# H08R7.net
KiCad netlist of a schematic drawn in EAGLE
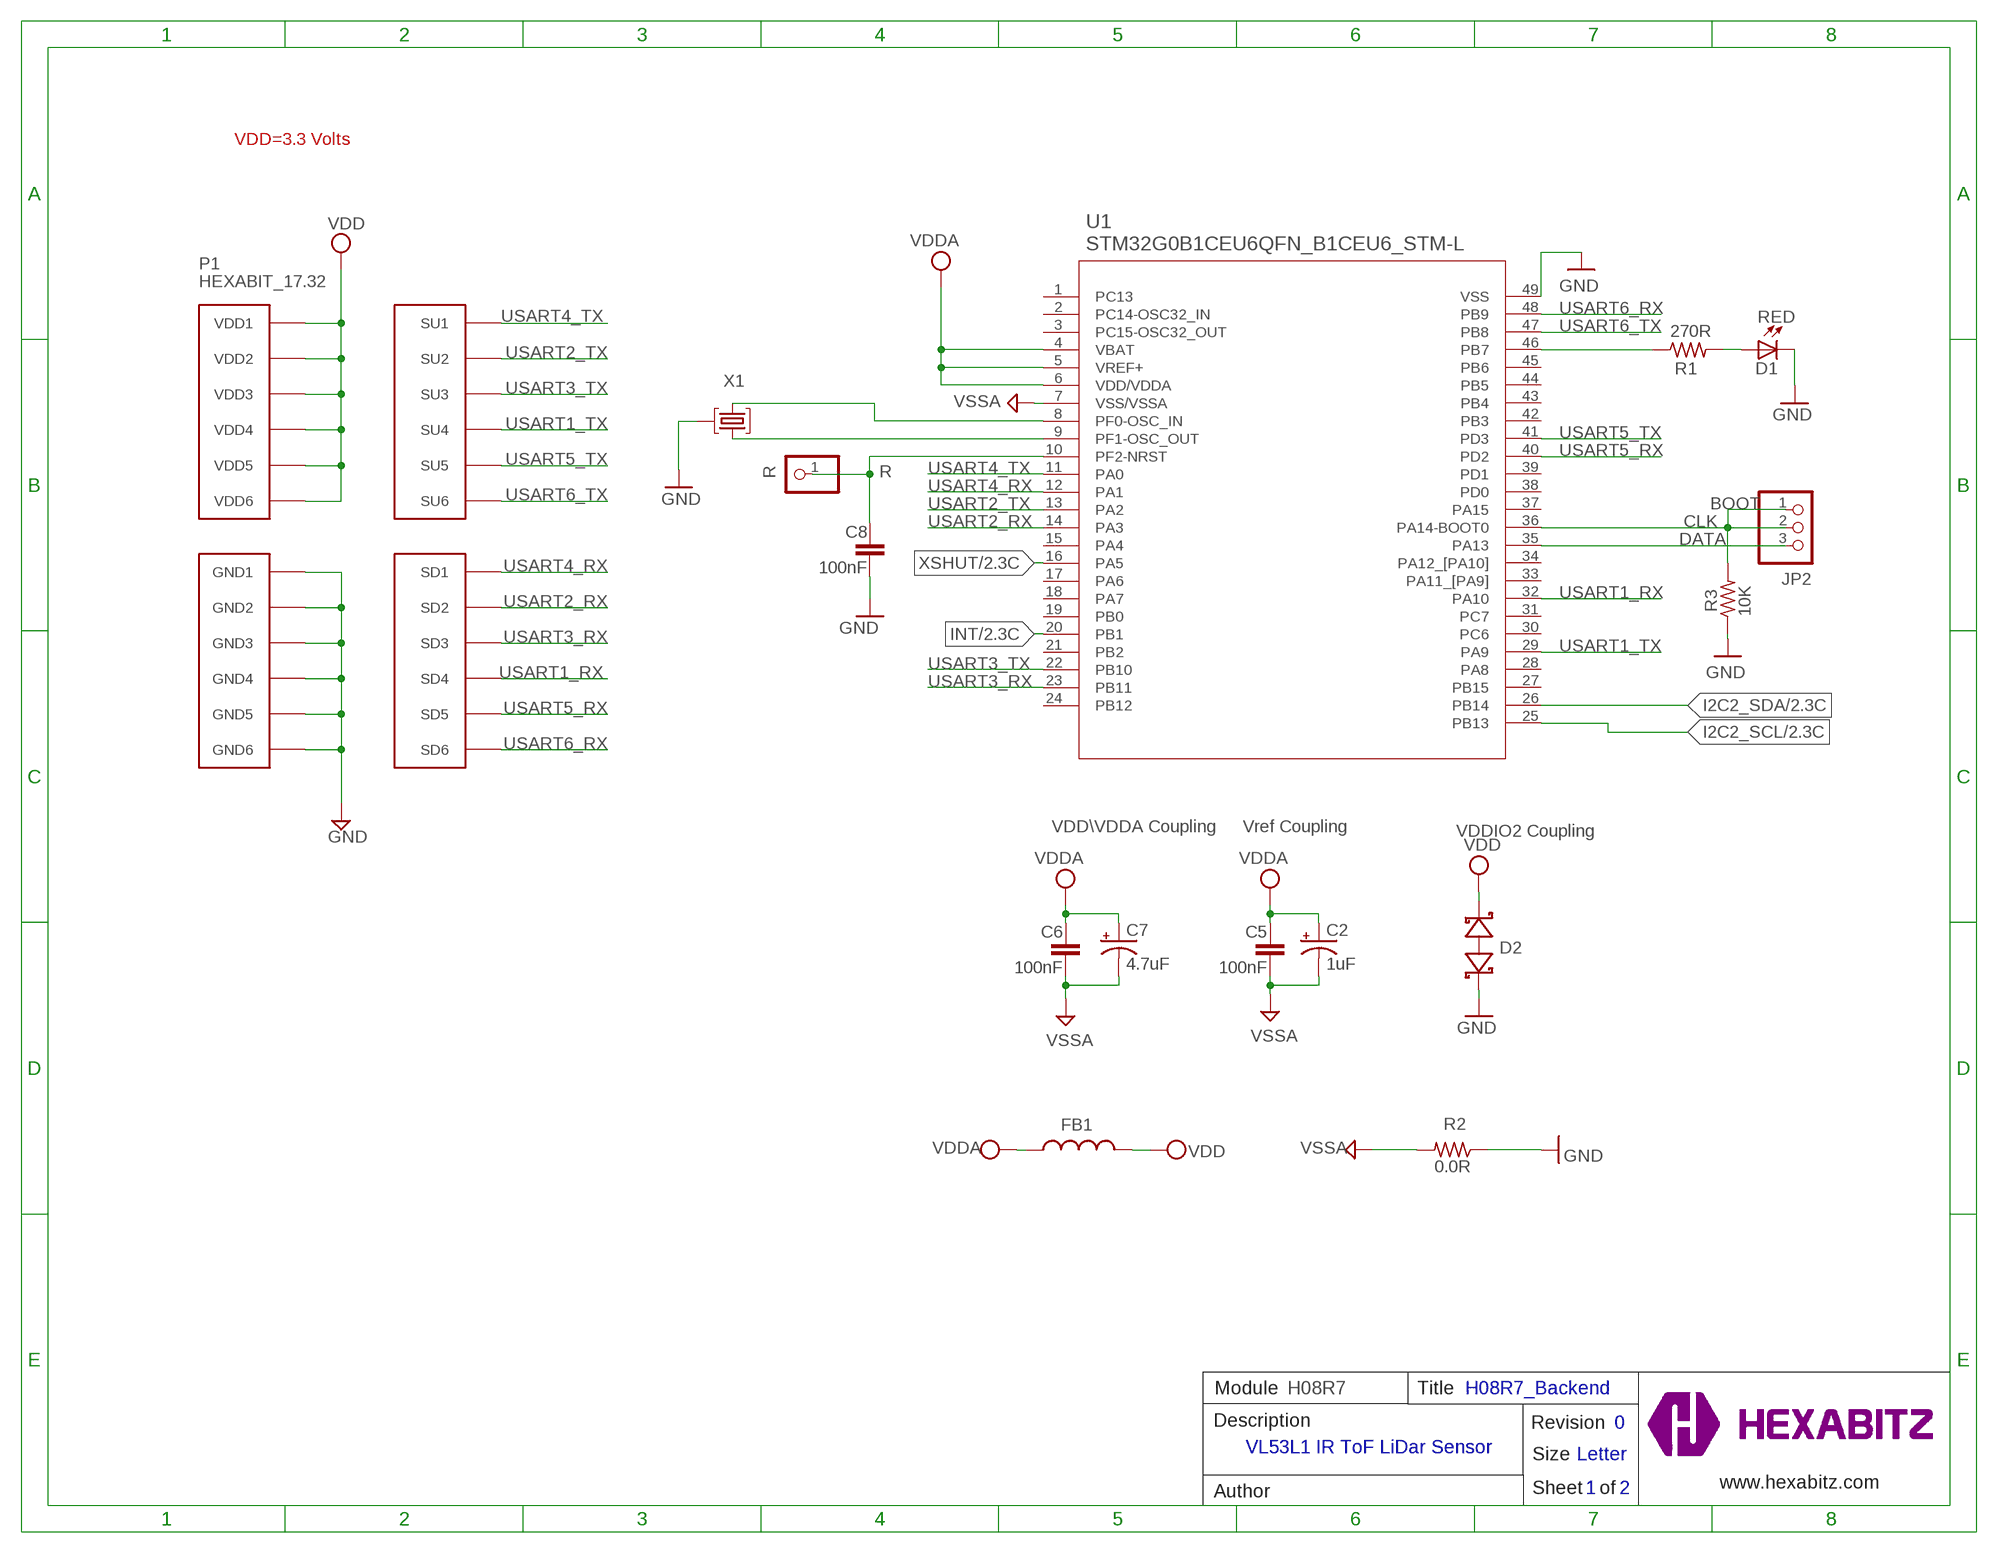
[diagram p0: schematic, sheet 1]
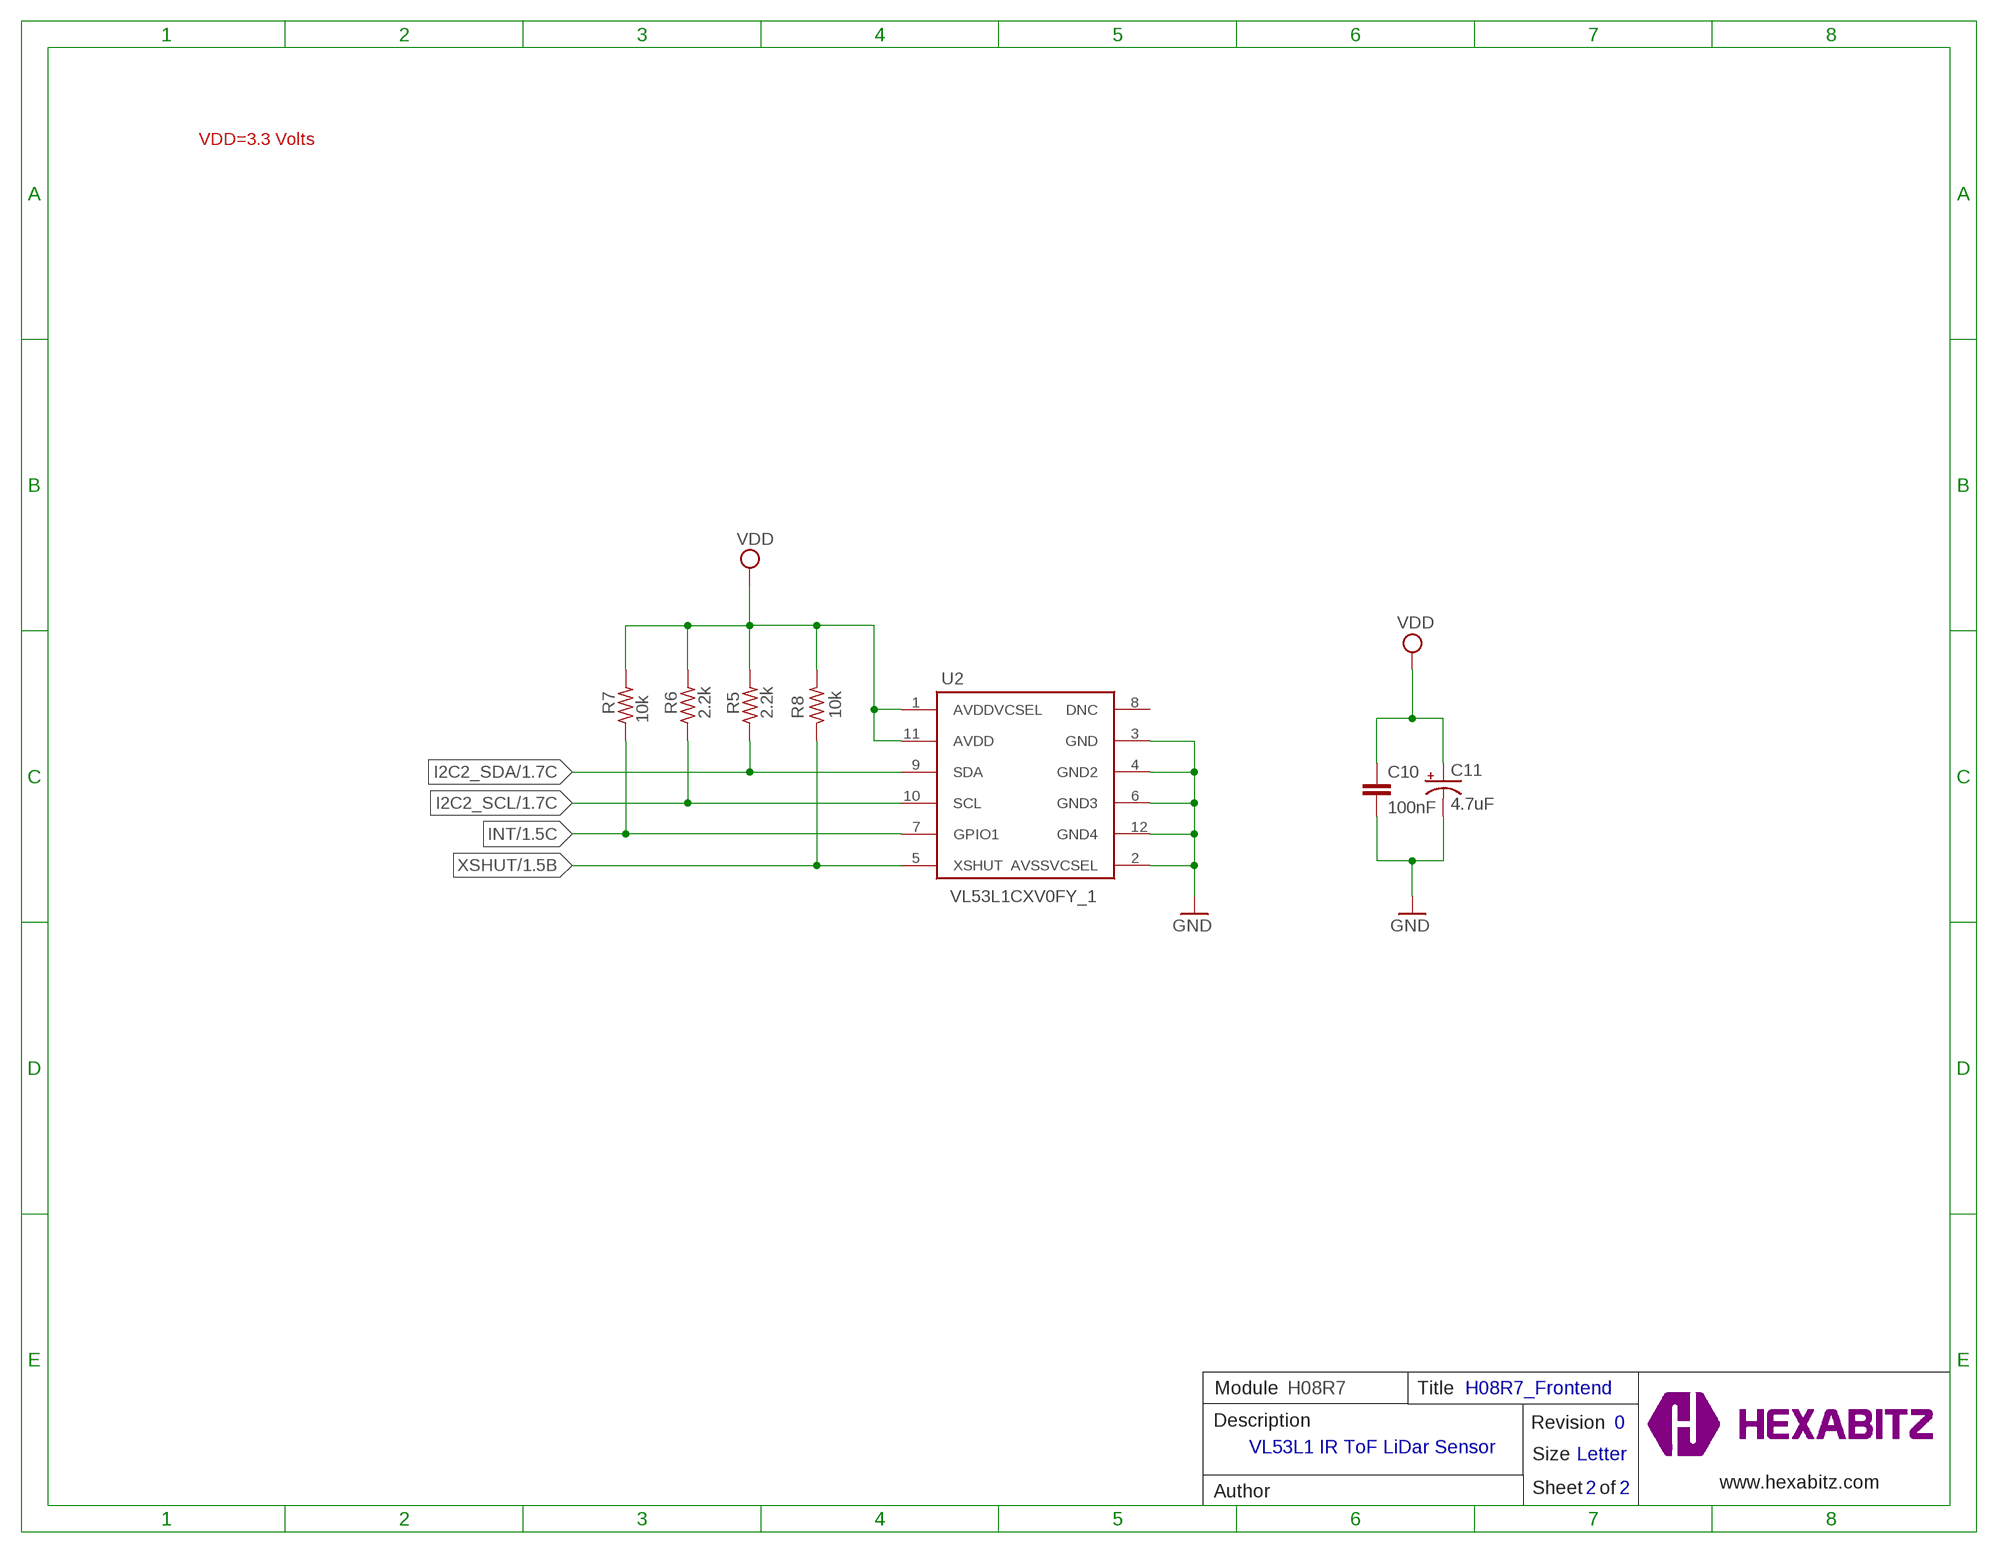
[diagram p1: schematic, sheet 2]

(export (version "E")
  (design (tool "Eeschema 10.0.6"))
  (components
    (comp (ref "C10")
      (value "100nF")
      (footprint "eagle-import:C-0603")
      (libsource (lib "eagle-import") (part "C-0603"))
    )
    (comp (ref "C11")
      (value "4.7uF")
      (footprint "eagle-import:C-0805-POL")
      (libsource (lib "eagle-import") (part "C-0805-POL"))
    )
    (comp (ref "R5")
      (value "2.2k")
      (footprint "eagle-import:R-0603")
      (libsource (lib "eagle-import") (part "R-0603"))
    )
    (comp (ref "R6")
      (value "2.2k")
      (footprint "eagle-import:R-0603")
      (libsource (lib "eagle-import") (part "R-0603"))
    )
    (comp (ref "R7")
      (value "10k")
      (footprint "eagle-import:R-0603")
      (libsource (lib "eagle-import") (part "R-0603"))
    )
    (comp (ref "R8")
      (value "10k")
      (footprint "eagle-import:R-0603")
      (libsource (lib "eagle-import") (part "R-0603"))
    )
    (comp (ref "U2")
      (value "VL53L1CXV0FY_1")
      (footprint "eagle-import:VL53L1CXV0FY1")
      (fields
        (field (name "MANUFACTURER_PART_NUMBER") "VL53L1CXV0FY/1")
        (field (name "MOUSER_PART_NUMBER") "511-VL53L1CXV0FY/1")
      )
      (libsource (lib "eagle-import") (part "VL53L1CXV0FY_1"))
    )
    (comp (ref "C2")
      (value "1uF")
      (footprint "eagle-import:C-0805-POL")
      (libsource (lib "eagle-import") (part "C-0805-POL"))
    )
    (comp (ref "C5")
      (value "100nF")
      (footprint "eagle-import:C-0603")
      (libsource (lib "eagle-import") (part "C-0603"))
    )
    (comp (ref "C6")
      (value "100nF")
      (footprint "eagle-import:C-0603")
      (libsource (lib "eagle-import") (part "C-0603"))
    )
    (comp (ref "C7")
      (value "4.7uF")
      (footprint "eagle-import:C-0805-POL")
      (libsource (lib "eagle-import") (part "C-0805-POL"))
    )
    (comp (ref "C8")
      (value "100nF")
      (footprint "eagle-import:C-0603")
      (libsource (lib "eagle-import") (part "C-0603"))
    )
    (comp (ref "D1")
      (value "RED")
      (footprint "eagle-import:VLMS1300-GS08")
      (fields
        (field (name "MPN") "VLMS1300-GS08")
        (field (name "MFN") "Vishay")
        (field (name "MPN_1") "VLMS1300-GS08")
        (field (name "OCTOPART_URL") "https://octopart.com/vlms1300-gs08-vishay-21709201?r=sp&s=_gcP4_q8T1SC6PJQPTQ9yA")
      )
      (libsource (lib "eagle-import") (part "VLMS1300-GS08"))
    )
    (comp (ref "D2")
      (value "BOURNS_CDSOD323-T03SCBOURNS_CDSOD323-T03SC_0_0")
      (footprint "eagle-import:BOURNS_CDSOD323-T03SC_0")
      (fields (field (name "MPN") "CDSOD323-T03SC"))
      (libsource (lib "eagle-import") (part "BOURNS_CDSOD323-T03SCBOURNS_CDSOD323-T03SC_0_0"))
    )
    (comp (ref "FB1")
      (value "FB-TDK_MMZ1608Y300B")
      (footprint "eagle-import:FB-TDK_MMZ1608Y300B")
      (fields
        (field (name "MFN") "TDK ")
        (field (name "MPN") "MMZ1608Y300B")
        (field (name "OCTOPART_URL") "https://octopart.com/mmz1608y300b-tdk-368280?r=sp&s=cd9_2ZEqQ9q9UNBuQgHAiA")
      )
      (libsource (lib "eagle-import") (part "FB-TDK_MMZ1608Y300B"))
    )
    (comp (ref "JP2")
      (value "PINHD-1X3")
      (footprint "eagle-import:1X03")
      (libsource (lib "eagle-import") (part "PINHD-1X3"))
    )
    (comp (ref "P1")
      (value "HEXABIT_17.32")
      (footprint "eagle-import:HEXABIT_17.32")
      (libsource (lib "eagle-import") (part "HEXABIT_?17.32"))
    )
    (comp (ref "R")
      (value "R")
      (footprint "eagle-import:1X01")
      (fields (field (name "MPN") "87227-1"))
      (libsource (lib "eagle-import") (part "PINHD-1X1"))
    )
    (comp (ref "R1")
      (value "270R")
      (footprint "eagle-import:R-0603")
      (libsource (lib "eagle-import") (part "R-0603"))
    )
    (comp (ref "R2")
      (value "0.0R")
      (footprint "eagle-import:R-0603")
      (fields
        (field (name "MFN") "Yageo")
        (field (name "MPN") "RC0603JR-070RL")
        (field (name "OCTOPART_URL") "https://octopart.com/rc0603jr-070rl-yageo-1241539?r=sp&s=X2NteqRjRNWrnx42Y0aliA")
        (field (name "RESISTANCE") "0.0 Ohm")
      )
      (libsource (lib "eagle-import") (part "R-0603"))
    )
    (comp (ref "R3")
      (value "10K")
      (footprint "eagle-import:R-0603")
      (libsource (lib "eagle-import") (part "R-0603"))
    )
    (comp (ref "TRIMBLE-LOGO1")
      (value "HEXA-LOGO")
      (footprint "eagle-import:HEXA-LOGO")
      (libsource (lib "eagle-import") (part "HEXA-LOGO"))
    )
    (comp (ref "U1")
      (value "STM32G0B1CEU6QFN_B1CEU6_STM-L")
      (footprint "eagle-import:QFN_B1CEU6_STM-L")
      (fields
        (field (name "MANUFACTURER_PART_NUMBER") "STM32G0B1CEU6")
        (field (name "COPYRIGHT") "Copyright (C) 2021 Ultra Librarian. All rights reserved.")
      )
      (libsource (lib "eagle-import") (part "STM32G0B1CEU6QFN_B1CEU6_STM-L"))
    )
    (comp (ref "X1")
      (value "XTALL_CSTCE8M00G52")
      (footprint "eagle-import:XTALL_CSTCE8M00G52")
      (fields (field (name "MPN") "CSTCE8M00G52Z-R0"))
      (libsource (lib "eagle-import") (part "XTALL_CSTCE8M00G52"))
    )
  )
  (nets
    (net (code "1") (name "CLK") (class "Default")
      (node (ref "JP2") (pin "1") (pinfunction "1_1") (pintype "passive"))
      (node (ref "JP2") (pin "2") (pinfunction "2_2") (pintype "passive"))
      (node (ref "R3") (pin "2") (pinfunction "2_2") (pintype "passive"))
      (node (ref "U1") (pin "36") (pinfunction "PA14-BOOT0_36") (pintype "bidirectional"))
    )
    (net (code "2") (name "DATA") (class "Default")
      (node (ref "JP2") (pin "3") (pinfunction "3_3") (pintype "passive"))
      (node (ref "U1") (pin "35") (pinfunction "PA13_35") (pintype "bidirectional"))
    )
    (net (code "3") (name "GND") (class "Default")
      (node (ref "C10") (pin "2") (pinfunction "2_2") (pintype "passive"))
      (node (ref "C11") (pin "2") (pinfunction "-_2") (pintype "passive"))
      (node (ref "C8") (pin "2") (pinfunction "2_2") (pintype "passive"))
      (node (ref "D1") (pin "C") (pinfunction "C_C") (pintype "passive"))
      (node (ref "D2") (pin "1") (pinfunction "A_1") (pintype "passive"))
      (node (ref "P1") (pin "PAD_PD10") (pinfunction "GND4_PAD_PD10") (pintype "power_in"))
      (node (ref "P1") (pin "PAD_PD11") (pinfunction "GND5_PAD_PD11") (pintype "power_in"))
      (node (ref "P1") (pin "PAD_PD12") (pinfunction "GND6_PAD_PD12") (pintype "power_in"))
      (node (ref "P1") (pin "PAD_PD7") (pinfunction "GND1_PAD_PD7") (pintype "power_in"))
      (node (ref "P1") (pin "PAD_PD8") (pinfunction "GND2_PAD_PD8") (pintype "power_in"))
      (node (ref "P1") (pin "PAD_PD9") (pinfunction "GND3_PAD_PD9") (pintype "power_in"))
      (node (ref "R2") (pin "1") (pinfunction "1_1") (pintype "passive"))
      (node (ref "R3") (pin "1") (pinfunction "1_1") (pintype "passive"))
      (node (ref "U1") (pin "49") (pinfunction "VSS_49") (pintype "passive"))
      (node (ref "U2") (pin "12") (pinfunction "GND4_12") (pintype "bidirectional"))
      (node (ref "U2") (pin "2") (pinfunction "AVSSVCSEL_2") (pintype "bidirectional"))
      (node (ref "U2") (pin "3") (pinfunction "GND_3") (pintype "bidirectional"))
      (node (ref "U2") (pin "4") (pinfunction "GND2_4") (pintype "bidirectional"))
      (node (ref "U2") (pin "6") (pinfunction "GND3_6") (pintype "bidirectional"))
      (node (ref "X1") (pin "P$2") (pinfunction "2_P$2") (pintype "passive"))
    )
    (net (code "4") (name "I2C2_SCL") (class "Default")
      (node (ref "R6") (pin "1") (pinfunction "1_1") (pintype "passive"))
      (node (ref "U1") (pin "25") (pinfunction "PB13_25") (pintype "bidirectional"))
      (node (ref "U2") (pin "10") (pinfunction "SCL_10") (pintype "bidirectional"))
    )
    (net (code "5") (name "I2C2_SDA") (class "Default")
      (node (ref "R5") (pin "1") (pinfunction "1_1") (pintype "passive"))
      (node (ref "U1") (pin "26") (pinfunction "PB14_26") (pintype "bidirectional"))
      (node (ref "U2") (pin "9") (pinfunction "SDA_9") (pintype "bidirectional"))
    )
    (net (code "6") (name "INT") (class "Default")
      (node (ref "R7") (pin "1") (pinfunction "1_1") (pintype "passive"))
      (node (ref "U1") (pin "20") (pinfunction "PB1_20") (pintype "bidirectional"))
      (node (ref "U2") (pin "7") (pinfunction "GPIO1_7") (pintype "bidirectional"))
    )
    (net (code "7") (name "Net-(D1-PadA)") (class "Default")
      (node (ref "D1") (pin "A") (pinfunction "A_A") (pintype "passive"))
      (node (ref "R1") (pin "2") (pinfunction "2_2") (pintype "passive"))
    )
    (net (code "8") (name "Net-(U1-PB7)") (class "Default")
      (node (ref "R1") (pin "1") (pinfunction "1_1") (pintype "passive"))
      (node (ref "U1") (pin "46") (pinfunction "PB7_46") (pintype "bidirectional"))
    )
    (net (code "9") (name "Net-(U1-PF0-OSC_IN)") (class "Default")
      (node (ref "U1") (pin "8") (pinfunction "PF0-OSC_IN_8") (pintype "bidirectional"))
      (node (ref "X1") (pin "P$3") (pinfunction "3_P$3") (pintype "passive"))
    )
    (net (code "10") (name "Net-(U1-PF1-OSC_OUT)") (class "Default")
      (node (ref "U1") (pin "9") (pinfunction "PF1-OSC_OUT_9") (pintype "output"))
      (node (ref "X1") (pin "P$1") (pinfunction "1_P$1") (pintype "passive"))
    )
    (net (code "11") (name "Net-(U1-PF2-NRST)") (class "Default")
      (node (ref "C8") (pin "1") (pinfunction "1_1") (pintype "passive"))
      (node (ref "R") (pin "1") (pinfunction "1_1") (pintype "passive"))
      (node (ref "U1") (pin "10") (pinfunction "PF2-NRST_10") (pintype "bidirectional"))
    )
    (net (code "12") (name "USART1_RX") (class "Default")
      (node (ref "P1") (pin "PAD_PD4") (pinfunction "SD4_PAD_PD4") (pintype "bidirectional"))
      (node (ref "U1") (pin "32") (pinfunction "PA10_32") (pintype "bidirectional"))
    )
    (net (code "13") (name "USART1_TX") (class "Default")
      (node (ref "P1") (pin "PAD_PU4") (pinfunction "SU4_PAD_PU4") (pintype "bidirectional"))
      (node (ref "U1") (pin "29") (pinfunction "PA9_29") (pintype "bidirectional"))
    )
    (net (code "14") (name "USART2_RX") (class "Default")
      (node (ref "P1") (pin "PAD_PD2") (pinfunction "SD2_PAD_PD2") (pintype "bidirectional"))
      (node (ref "U1") (pin "14") (pinfunction "PA3_14") (pintype "bidirectional"))
    )
    (net (code "15") (name "USART2_TX") (class "Default")
      (node (ref "P1") (pin "PAD_PU2") (pinfunction "SU2_PAD_PU2") (pintype "bidirectional"))
      (node (ref "U1") (pin "13") (pinfunction "PA2_13") (pintype "bidirectional"))
    )
    (net (code "16") (name "USART3_RX") (class "Default")
      (node (ref "P1") (pin "PAD_PD3") (pinfunction "SD3_PAD_PD3") (pintype "bidirectional"))
      (node (ref "U1") (pin "23") (pinfunction "PB11_23") (pintype "bidirectional"))
    )
    (net (code "17") (name "USART3_TX") (class "Default")
      (node (ref "P1") (pin "PAD_PU3") (pinfunction "SU3_PAD_PU3") (pintype "bidirectional"))
      (node (ref "U1") (pin "22") (pinfunction "PB10_22") (pintype "bidirectional"))
    )
    (net (code "18") (name "USART4_RX") (class "Default")
      (node (ref "P1") (pin "PAD_PD1") (pinfunction "SD1_PAD_PD1") (pintype "bidirectional"))
      (node (ref "U1") (pin "12") (pinfunction "PA1_12") (pintype "bidirectional"))
    )
    (net (code "19") (name "USART4_TX") (class "Default")
      (node (ref "P1") (pin "PAD_PU1") (pinfunction "SU1_PAD_PU1") (pintype "bidirectional"))
      (node (ref "U1") (pin "11") (pinfunction "PA0_11") (pintype "bidirectional"))
    )
    (net (code "20") (name "USART5_RX") (class "Default")
      (node (ref "P1") (pin "PAD_PD5") (pinfunction "SD5_PAD_PD5") (pintype "bidirectional"))
      (node (ref "U1") (pin "40") (pinfunction "PD2_40") (pintype "bidirectional"))
    )
    (net (code "21") (name "USART5_TX") (class "Default")
      (node (ref "P1") (pin "PAD_PU5") (pinfunction "SU5_PAD_PU5") (pintype "bidirectional"))
      (node (ref "U1") (pin "41") (pinfunction "PD3_41") (pintype "bidirectional"))
    )
    (net (code "22") (name "USART6_RX") (class "Default")
      (node (ref "P1") (pin "PAD_PD6") (pinfunction "SD6_PAD_PD6") (pintype "bidirectional"))
      (node (ref "U1") (pin "48") (pinfunction "PB9_48") (pintype "bidirectional"))
    )
    (net (code "23") (name "USART6_TX") (class "Default")
      (node (ref "P1") (pin "PAD_PU6") (pinfunction "SU6_PAD_PU6") (pintype "bidirectional"))
      (node (ref "U1") (pin "47") (pinfunction "PB8_47") (pintype "bidirectional"))
    )
    (net (code "24") (name "VDD") (class "Default")
      (node (ref "C10") (pin "1") (pinfunction "1_1") (pintype "passive"))
      (node (ref "C11") (pin "1") (pinfunction "+_1") (pintype "passive"))
      (node (ref "D2") (pin "2") (pinfunction "C_2") (pintype "passive"))
      (node (ref "FB1") (pin "2") (pinfunction "2_2") (pintype "passive"))
      (node (ref "P1") (pin "PAD_PU10") (pinfunction "VDD4_PAD_PU10") (pintype "power_in"))
      (node (ref "P1") (pin "PAD_PU11") (pinfunction "VDD5_PAD_PU11") (pintype "power_in"))
      (node (ref "P1") (pin "PAD_PU12") (pinfunction "VDD6_PAD_PU12") (pintype "power_in"))
      (node (ref "P1") (pin "PAD_PU7") (pinfunction "VDD1_PAD_PU7") (pintype "power_in"))
      (node (ref "P1") (pin "PAD_PU8") (pinfunction "VDD2_PAD_PU8") (pintype "power_in"))
      (node (ref "P1") (pin "PAD_PU9") (pinfunction "VDD3_PAD_PU9") (pintype "power_in"))
      (node (ref "R5") (pin "2") (pinfunction "2_2") (pintype "passive"))
      (node (ref "R6") (pin "2") (pinfunction "2_2") (pintype "passive"))
      (node (ref "R7") (pin "2") (pinfunction "2_2") (pintype "passive"))
      (node (ref "R8") (pin "2") (pinfunction "2_2") (pintype "passive"))
      (node (ref "U2") (pin "1") (pinfunction "AVDDVCSEL_1") (pintype "bidirectional"))
      (node (ref "U2") (pin "11") (pinfunction "AVDD_11") (pintype "bidirectional"))
    )
    (net (code "25") (name "VDDA") (class "Default")
      (node (ref "C2") (pin "1") (pinfunction "+_1") (pintype "passive"))
      (node (ref "C5") (pin "1") (pinfunction "1_1") (pintype "passive"))
      (node (ref "C6") (pin "1") (pinfunction "1_1") (pintype "passive"))
      (node (ref "C7") (pin "1") (pinfunction "+_1") (pintype "passive"))
      (node (ref "FB1") (pin "1") (pinfunction "1_1") (pintype "passive"))
      (node (ref "U1") (pin "4") (pinfunction "VBAT_4") (pintype "passive"))
      (node (ref "U1") (pin "5") (pinfunction "VREF+_5") (pintype "power_in"))
      (node (ref "U1") (pin "6") (pinfunction "VDD/VDDA_6") (pintype "power_in"))
    )
    (net (code "26") (name "VSSA") (class "Default")
      (node (ref "C2") (pin "2") (pinfunction "-_2") (pintype "passive"))
      (node (ref "C5") (pin "2") (pinfunction "2_2") (pintype "passive"))
      (node (ref "C6") (pin "2") (pinfunction "2_2") (pintype "passive"))
      (node (ref "C7") (pin "2") (pinfunction "-_2") (pintype "passive"))
      (node (ref "R2") (pin "2") (pinfunction "2_2") (pintype "passive"))
      (node (ref "U1") (pin "7") (pinfunction "VSS/VSSA_7") (pintype "passive"))
    )
    (net (code "27") (name "XSHUT") (class "Default")
      (node (ref "R8") (pin "1") (pinfunction "1_1") (pintype "passive"))
      (node (ref "U1") (pin "16") (pinfunction "PA5_16") (pintype "bidirectional"))
      (node (ref "U2") (pin "5") (pinfunction "XSHUT_5") (pintype "bidirectional"))
    )
    (net (code "28") (name "unconnected-(U1-PA4-Pad15)") (class "Default")
      (node (ref "U1") (pin "15") (pinfunction "PA4_15") (pintype "bidirectional"))
    )
    (net (code "29") (name "unconnected-(U1-PA6-Pad17)") (class "Default")
      (node (ref "U1") (pin "17") (pinfunction "PA6_17") (pintype "bidirectional"))
    )
    (net (code "30") (name "unconnected-(U1-PA7-Pad18)") (class "Default")
      (node (ref "U1") (pin "18") (pinfunction "PA7_18") (pintype "bidirectional"))
    )
    (net (code "31") (name "unconnected-(U1-PA8-Pad28)") (class "Default")
      (node (ref "U1") (pin "28") (pinfunction "PA8_28") (pintype "bidirectional"))
    )
    (net (code "32") (name "unconnected-(U1-PA11_[PA9]-Pad33)") (class "Default")
      (node (ref "U1") (pin "33") (pinfunction "PA11_[PA9]_33") (pintype "bidirectional"))
    )
    (net (code "33") (name "unconnected-(U1-PA12_[PA10]-Pad34)") (class "Default")
      (node (ref "U1") (pin "34") (pinfunction "PA12_[PA10]_34") (pintype "bidirectional"))
    )
    (net (code "34") (name "unconnected-(U1-PA15-Pad37)") (class "Default")
      (node (ref "U1") (pin "37") (pinfunction "PA15_37") (pintype "bidirectional"))
    )
    (net (code "35") (name "unconnected-(U1-PB0-Pad19)") (class "Default")
      (node (ref "U1") (pin "19") (pinfunction "PB0_19") (pintype "bidirectional"))
    )
    (net (code "36") (name "unconnected-(U1-PB2-Pad21)") (class "Default")
      (node (ref "U1") (pin "21") (pinfunction "PB2_21") (pintype "bidirectional"))
    )
    (net (code "37") (name "unconnected-(U1-PB3-Pad42)") (class "Default")
      (node (ref "U1") (pin "42") (pinfunction "PB3_42") (pintype "bidirectional"))
    )
    (net (code "38") (name "unconnected-(U1-PB4-Pad43)") (class "Default")
      (node (ref "U1") (pin "43") (pinfunction "PB4_43") (pintype "bidirectional"))
    )
    (net (code "39") (name "unconnected-(U1-PB5-Pad44)") (class "Default")
      (node (ref "U1") (pin "44") (pinfunction "PB5_44") (pintype "bidirectional"))
    )
    (net (code "40") (name "unconnected-(U1-PB6-Pad45)") (class "Default")
      (node (ref "U1") (pin "45") (pinfunction "PB6_45") (pintype "bidirectional"))
    )
    (net (code "41") (name "unconnected-(U1-PB12-Pad24)") (class "Default")
      (node (ref "U1") (pin "24") (pinfunction "PB12_24") (pintype "bidirectional"))
    )
    (net (code "42") (name "unconnected-(U1-PB15-Pad27)") (class "Default")
      (node (ref "U1") (pin "27") (pinfunction "PB15_27") (pintype "bidirectional"))
    )
    (net (code "43") (name "unconnected-(U1-PC6-Pad30)") (class "Default")
      (node (ref "U1") (pin "30") (pinfunction "PC6_30") (pintype "bidirectional"))
    )
    (net (code "44") (name "unconnected-(U1-PC7-Pad31)") (class "Default")
      (node (ref "U1") (pin "31") (pinfunction "PC7_31") (pintype "bidirectional"))
    )
    (net (code "45") (name "unconnected-(U1-PC13-Pad1)") (class "Default")
      (node (ref "U1") (pin "1") (pinfunction "PC13_1") (pintype "bidirectional"))
    )
    (net (code "46") (name "unconnected-(U1-PC14-OSC32_IN-Pad2)") (class "Default")
      (node (ref "U1") (pin "2") (pinfunction "PC14-OSC32_IN_2") (pintype "bidirectional"))
    )
    (net (code "47") (name "unconnected-(U1-PC15-OSC32_OUT-Pad3)") (class "Default")
      (node (ref "U1") (pin "3") (pinfunction "PC15-OSC32_OUT_3") (pintype "output"))
    )
    (net (code "48") (name "unconnected-(U1-PD0-Pad38)") (class "Default")
      (node (ref "U1") (pin "38") (pinfunction "PD0_38") (pintype "bidirectional"))
    )
    (net (code "49") (name "unconnected-(U1-PD1-Pad39)") (class "Default")
      (node (ref "U1") (pin "39") (pinfunction "PD1_39") (pintype "bidirectional"))
    )
    (net (code "50") (name "unconnected-(U2-DNC-Pad8)") (class "Default")
      (node (ref "U2") (pin "8") (pinfunction "DNC_8") (pintype "no_connect"))
    )
  )
)
